# Connective.net
KiCad netlist of a schematic drawn in EasyEDA Pro
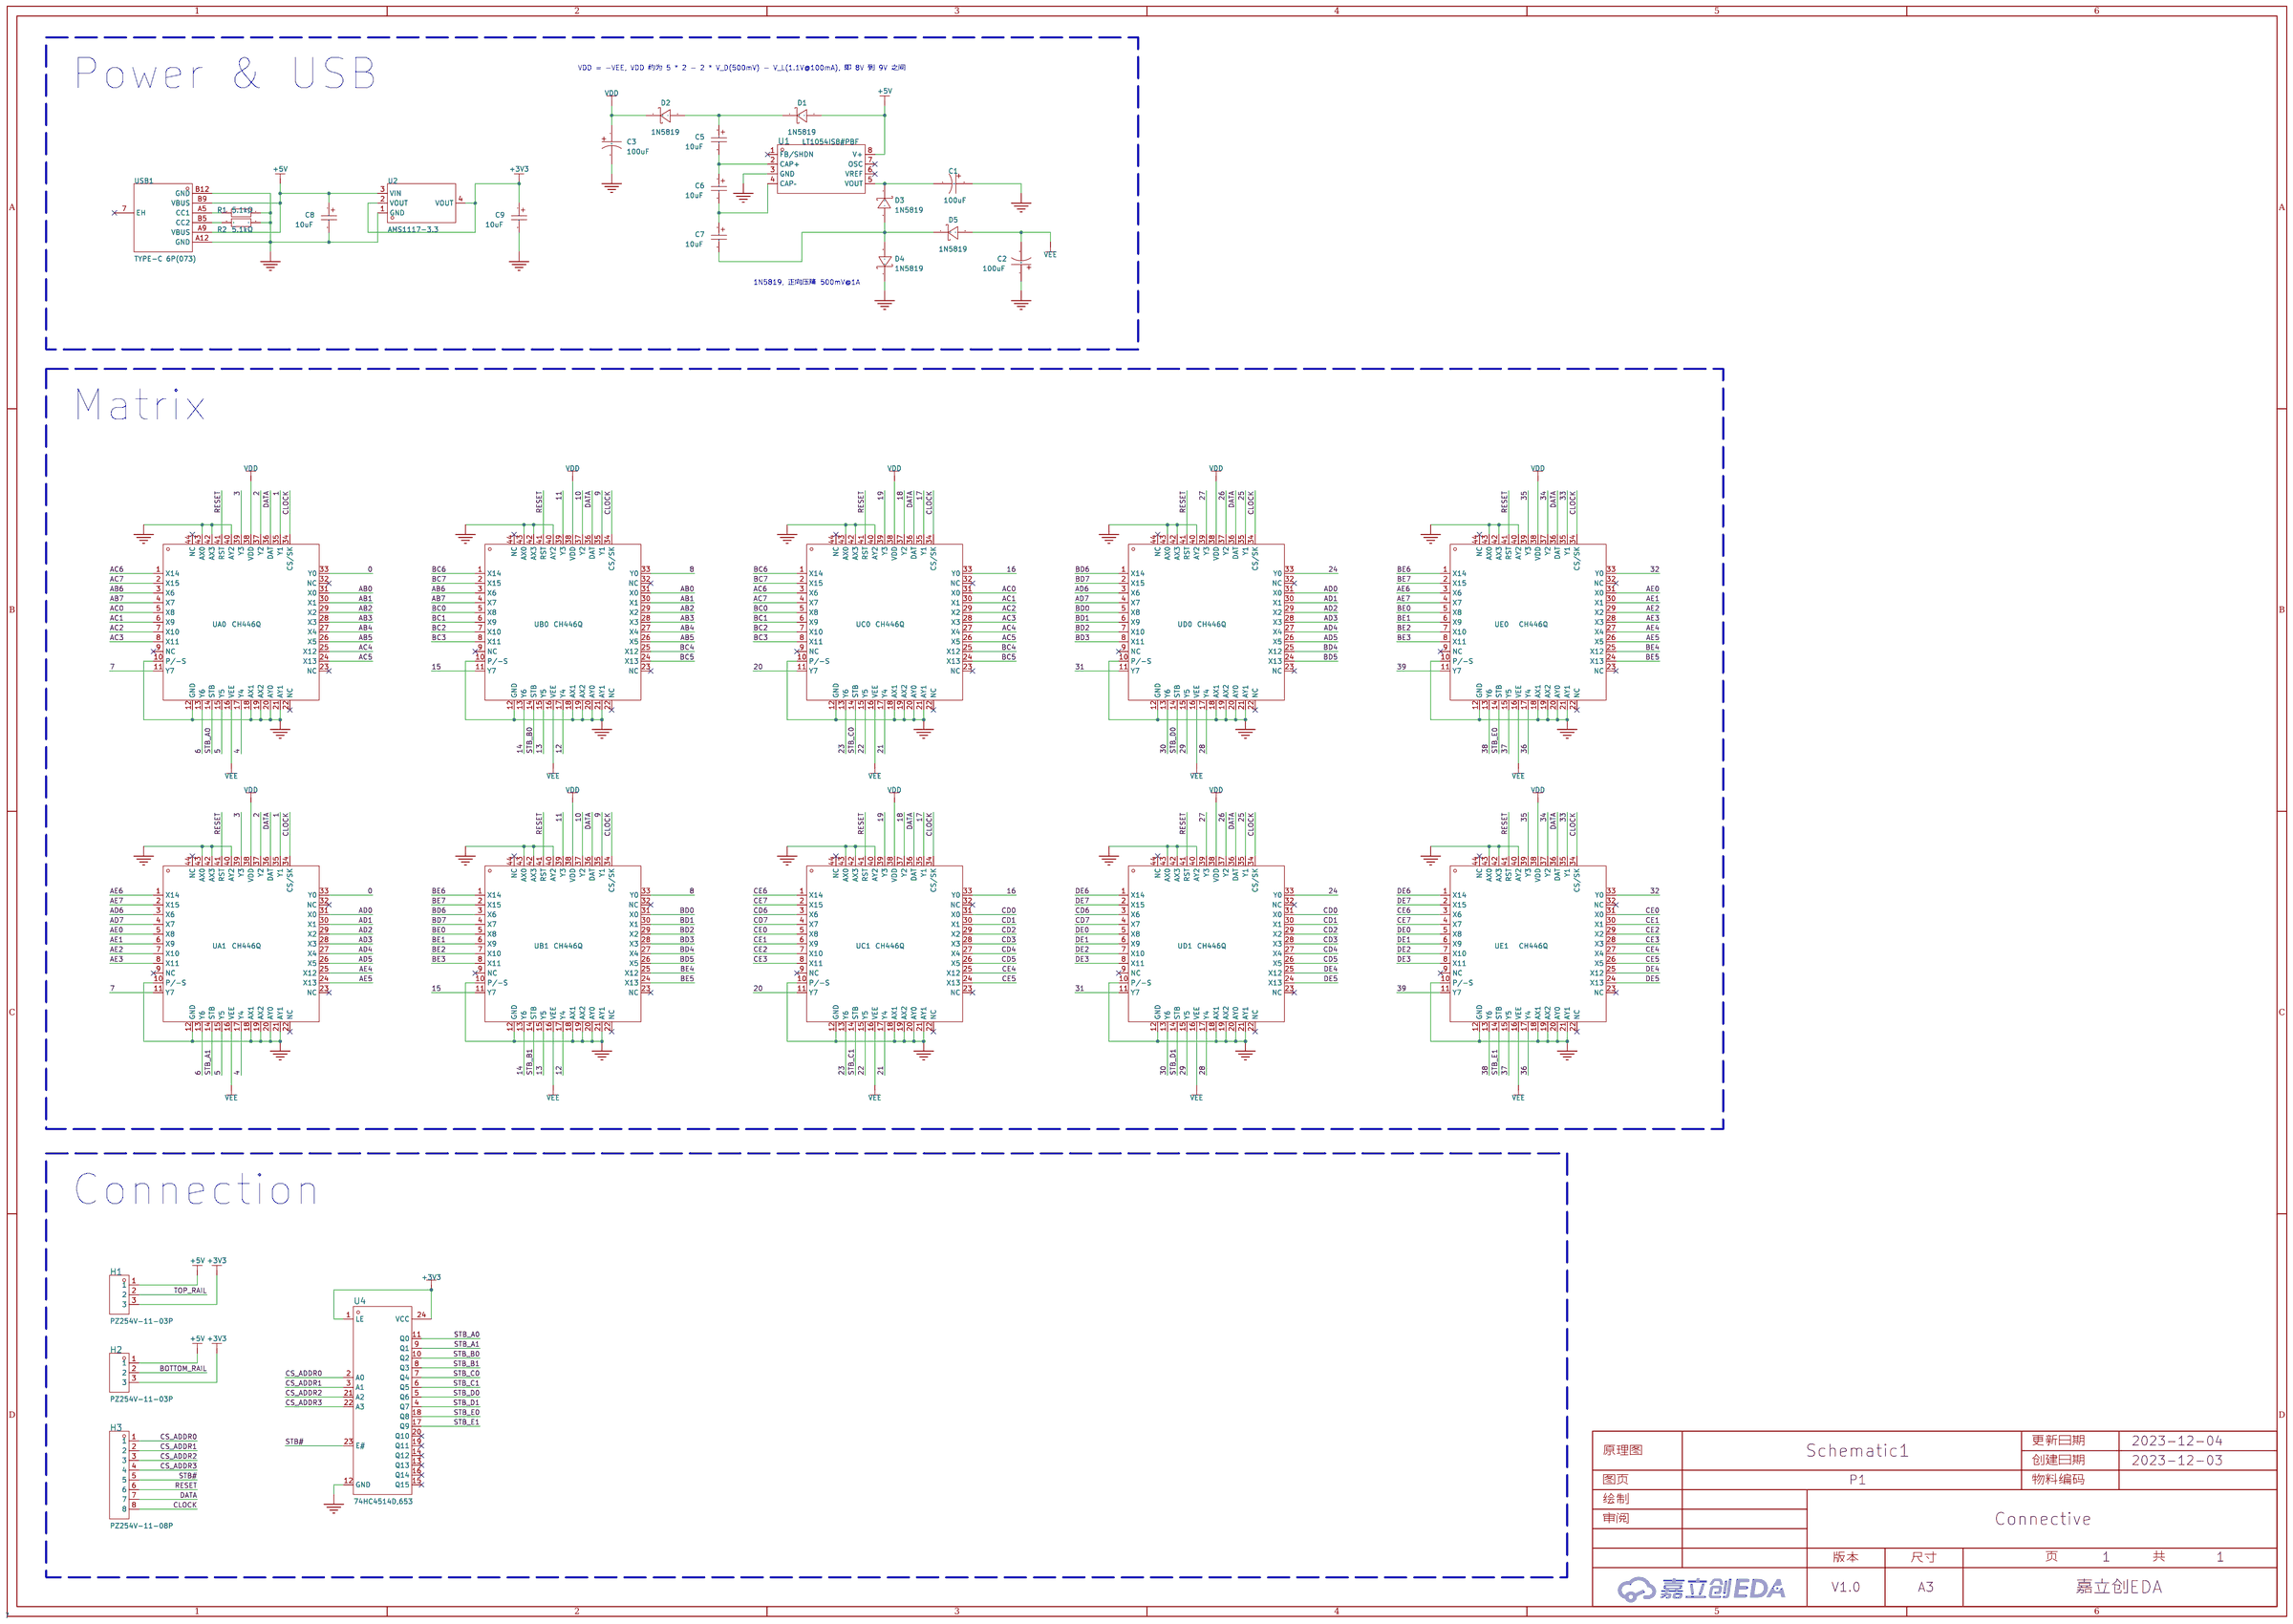
[diagram p0: schematic sheet]

(export (version "E")
  (design (tool "Eeschema 10.0.6"))
  (components
    (comp (ref "C1")
      (value "100uF")
      (footprint "easyedapro:CAP-SMD_L3.5-W2.8")
      (description "容值:100uF;精度:±20%;额定电压:10V;等效串联电阻:3Ω@100kHz;")
      (fields (field (name "Manufacturer Part") "CA45-107M010BT") (field (name "Manufacturer") "TANCAP(容电)"))
      (libsource (lib "easyedapro") (part "CA45-107M010BT"))
    )
    (comp (ref "C2")
      (value "100uF")
      (footprint "easyedapro:CAP-SMD_L3.5-W2.8")
      (description "容值:100uF;精度:±20%;额定电压:10V;等效串联电阻:3Ω@100kHz;")
      (fields (field (name "Manufacturer Part") "CA45-107M010BT") (field (name "Manufacturer") "TANCAP(容电)"))
      (libsource (lib "easyedapro") (part "CA45-107M010BT"))
    )
    (comp (ref "C3")
      (value "100uF")
      (footprint "easyedapro:CAP-SMD_L3.5-W2.8")
      (description "容值:100uF;精度:±20%;额定电压:10V;等效串联电阻:3Ω@100kHz;")
      (fields (field (name "Manufacturer Part") "CA45-107M010BT") (field (name "Manufacturer") "TANCAP(容电)"))
      (libsource (lib "easyedapro") (part "CA45-107M010BT"))
    )
    (comp (ref "C5")
      (value "10uF")
      (footprint "easyedapro:CAP-SMD_L3.2-W1.6-RD")
      (description "容值:10uF;精度:±10%;额定电压:16V;等效串联电阻:10Ω@100kHz;")
      (fields
        (field (name "Manufacturer Part") "CA45-A-16V-10uF-K")
        (field (name "Manufacturer") "CEC(振华新云)")
      )
      (libsource (lib "easyedapro") (part "CA45-A-16V-10UF-K"))
    )
    (comp (ref "C6")
      (value "10uF")
      (footprint "easyedapro:CAP-SMD_L3.2-W1.6-RD")
      (description "容值:10uF;精度:±10%;额定电压:16V;等效串联电阻:10Ω@100kHz;")
      (fields
        (field (name "Manufacturer Part") "CA45-A-16V-10uF-K")
        (field (name "Manufacturer") "CEC(振华新云)")
      )
      (libsource (lib "easyedapro") (part "CA45-A-16V-10UF-K"))
    )
    (comp (ref "C7")
      (value "10uF")
      (footprint "easyedapro:CAP-SMD_L3.2-W1.6-RD")
      (description "容值:10uF;精度:±10%;额定电压:16V;等效串联电阻:10Ω@100kHz;")
      (fields
        (field (name "Manufacturer Part") "CA45-A-16V-10uF-K")
        (field (name "Manufacturer") "CEC(振华新云)")
      )
      (libsource (lib "easyedapro") (part "CA45-A-16V-10UF-K"))
    )
    (comp (ref "C8")
      (value "10uF")
      (footprint "easyedapro:CAP-SMD_L3.2-W1.6-RD")
      (description "容值:10uF;精度:±10%;额定电压:16V;等效串联电阻:10Ω@100kHz;")
      (fields
        (field (name "Manufacturer Part") "CA45-A-16V-10uF-K")
        (field (name "Manufacturer") "CEC(振华新云)")
      )
      (libsource (lib "easyedapro") (part "CA45-A-16V-10UF-K"))
    )
    (comp (ref "C9")
      (value "10uF")
      (footprint "easyedapro:CAP-SMD_L3.2-W1.6-RD")
      (description "容值:10uF;精度:±10%;额定电压:16V;等效串联电阻:10Ω@100kHz;")
      (fields
        (field (name "Manufacturer Part") "CA45-A-16V-10uF-K")
        (field (name "Manufacturer") "CEC(振华新云)")
      )
      (libsource (lib "easyedapro") (part "CA45-A-16V-10UF-K"))
    )
    (comp (ref "D1")
      (value "1N5819")
      (footprint "easyedapro:SMA_L4.4-W2.6-LS5.0-RD")
      (description "直流反向耐压(Vr):40V;平均整流电流(Io):1A;正向压降(Vf):500mV@1A;")
      (fields (field (name "Manufacturer") "KEXIN(科信)"))
      (libsource (lib "easyedapro") (part "1N5819_C437199"))
    )
    (comp (ref "D2")
      (value "1N5819")
      (footprint "easyedapro:SMA_L4.4-W2.6-LS5.0-RD")
      (description "直流反向耐压(Vr):40V;平均整流电流(Io):1A;正向压降(Vf):500mV@1A;")
      (fields (field (name "Manufacturer") "KEXIN(科信)"))
      (libsource (lib "easyedapro") (part "1N5819_C437199"))
    )
    (comp (ref "D3")
      (value "1N5819")
      (footprint "easyedapro:SMA_L4.4-W2.6-LS5.0-RD")
      (description "直流反向耐压(Vr):40V;平均整流电流(Io):1A;正向压降(Vf):500mV@1A;")
      (fields (field (name "Manufacturer") "KEXIN(科信)"))
      (libsource (lib "easyedapro") (part "1N5819_C437199"))
    )
    (comp (ref "D4")
      (value "1N5819")
      (footprint "easyedapro:SMA_L4.4-W2.6-LS5.0-RD")
      (description "直流反向耐压(Vr):40V;平均整流电流(Io):1A;正向压降(Vf):500mV@1A;")
      (fields (field (name "Manufacturer") "KEXIN(科信)"))
      (libsource (lib "easyedapro") (part "1N5819_C437199"))
    )
    (comp (ref "D5")
      (value "1N5819")
      (footprint "easyedapro:SMA_L4.4-W2.6-LS5.0-RD")
      (description "直流反向耐压(Vr):40V;平均整流电流(Io):1A;正向压降(Vf):500mV@1A;")
      (fields (field (name "Manufacturer") "KEXIN(科信)"))
      (libsource (lib "easyedapro") (part "1N5819_C437199"))
    )
    (comp (ref "H1")
      (value "PZ254V-11-03P")
      (footprint "easyedapro:HDR-TH_3P-P2.54-V-M")
      (fields (field (name "Manufacturer") "XFCN(兴飞)"))
      (libsource (lib "easyedapro") (part "PZ254V-11-03P_C2937625"))
    )
    (comp (ref "H2")
      (value "PZ254V-11-03P")
      (footprint "easyedapro:HDR-TH_3P-P2.54-V-M")
      (fields (field (name "Manufacturer") "XFCN(兴飞)"))
      (libsource (lib "easyedapro") (part "PZ254V-11-03P_C2937625"))
    )
    (comp (ref "H3")
      (value "PZ254V-11-08P")
      (footprint "easyedapro:HDR-TH_8P-P2.54-V-M")
      (fields (field (name "Manufacturer") "XFCN(兴飞)"))
      (libsource (lib "easyedapro") (part "PZ254V-11-08P"))
    )
    (comp (ref "R1")
      (value "5.1kΩ")
      (footprint "easyedapro:R0603")
      (description "阻值:5.1kΩ;精度:±1%;功率:100mW;温度系数:±100ppm/°C;电阻类型:厚膜电阻;")
      (fields
        (field (name "Manufacturer Part") "0603WAF5101T5E")
        (field (name "Manufacturer") "UNI-ROYAL(厚声)")
      )
      (libsource (lib "easyedapro") (part "0603WAF5101T5E"))
    )
    (comp (ref "R2")
      (value "5.1kΩ")
      (footprint "easyedapro:R0603")
      (description "阻值:5.1kΩ;精度:±1%;功率:100mW;温度系数:±100ppm/°C;电阻类型:厚膜电阻;")
      (fields
        (field (name "Manufacturer Part") "0603WAF5101T5E")
        (field (name "Manufacturer") "UNI-ROYAL(厚声)")
      )
      (libsource (lib "easyedapro") (part "0603WAF5101T5E"))
    )
    (comp (ref "U1")
      (value "LT1054IS8#PBF")
      (footprint "easyedapro:SO-8_L4.9-W3.9-P1.27-LS6.0-BL")
      (description "功能类型:升压型;输出类型:可调和固定;输入电压:3.5V~15V;输出电压:2.5V~30V;输出电流(最大值):100mA;")
      (fields (field (name "Manufacturer") "ADI(亚德诺)"))
      (libsource (lib "easyedapro") (part "LT1054IS8#PBF"))
    )
    (comp (ref "U2")
      (value "AMS1117-3.3")
      (footprint "easyedapro:SOT-223-3_L6.5-W3.4-P2.30-LS7.0-BR")
      (description "输出类型:固定;最大输入电压:-;输出电压:3.3V;输出电流:1A;电源纹波抑制比(PSRR):72dB@(120Hz);输出极性:正;")
      (fields (field (name "Manufacturer") "AMS"))
      (libsource (lib "easyedapro") (part "AMS1117-3.3"))
    )
    (comp (ref "U4")
      (value "74HC4514D,653")
      (footprint "easyedapro:SOIC-24_L15.4-W7.5-P1.27-LS10.3-BL")
      (description "灌电流(IOL):5.2mA;拉电流(IOH):5.2mA;供电电压:2V~6V;")
      (fields (field (name "Manufacturer") "Nexperia(安世)"))
      (libsource (lib "easyedapro") (part "74HC4514D"))
    )
    (comp (ref "UA0")
      (value "CH446Q")
      (footprint "easyedapro:LQFP-44_L10.0-W10.0-P0.80-LS12.0-BL")
      (description "开关电路:-;")
      (fields (field (name "Manufacturer") "WCH(南京沁恒)"))
      (libsource (lib "easyedapro") (part "CH446Q"))
    )
    (comp (ref "UA1")
      (value "CH446Q")
      (footprint "easyedapro:LQFP-44_L10.0-W10.0-P0.80-LS12.0-BL")
      (description "开关电路:-;")
      (fields (field (name "Manufacturer") "WCH(南京沁恒)"))
      (libsource (lib "easyedapro") (part "CH446Q"))
    )
    (comp (ref "UB0")
      (value "CH446Q")
      (footprint "easyedapro:LQFP-44_L10.0-W10.0-P0.80-LS12.0-BL")
      (description "开关电路:-;")
      (fields (field (name "Manufacturer") "WCH(南京沁恒)"))
      (libsource (lib "easyedapro") (part "CH446Q"))
    )
    (comp (ref "UB1")
      (value "CH446Q")
      (footprint "easyedapro:LQFP-44_L10.0-W10.0-P0.80-LS12.0-BL")
      (description "开关电路:-;")
      (fields (field (name "Manufacturer") "WCH(南京沁恒)"))
      (libsource (lib "easyedapro") (part "CH446Q"))
    )
    (comp (ref "UC0")
      (value "CH446Q")
      (footprint "easyedapro:LQFP-44_L10.0-W10.0-P0.80-LS12.0-BL")
      (description "开关电路:-;")
      (fields (field (name "Manufacturer") "WCH(南京沁恒)"))
      (libsource (lib "easyedapro") (part "CH446Q"))
    )
    (comp (ref "UC1")
      (value "CH446Q")
      (footprint "easyedapro:LQFP-44_L10.0-W10.0-P0.80-LS12.0-BL")
      (description "开关电路:-;")
      (fields (field (name "Manufacturer") "WCH(南京沁恒)"))
      (libsource (lib "easyedapro") (part "CH446Q"))
    )
    (comp (ref "UD0")
      (value "CH446Q")
      (footprint "easyedapro:LQFP-44_L10.0-W10.0-P0.80-LS12.0-BL")
      (description "开关电路:-;")
      (fields (field (name "Manufacturer") "WCH(南京沁恒)"))
      (libsource (lib "easyedapro") (part "CH446Q"))
    )
    (comp (ref "UD1")
      (value "CH446Q")
      (footprint "easyedapro:LQFP-44_L10.0-W10.0-P0.80-LS12.0-BL")
      (description "开关电路:-;")
      (fields (field (name "Manufacturer") "WCH(南京沁恒)"))
      (libsource (lib "easyedapro") (part "CH446Q"))
    )
    (comp (ref "UE0")
      (value "CH446Q")
      (footprint "easyedapro:LQFP-44_L10.0-W10.0-P0.80-LS12.0-BL")
      (description "开关电路:-;")
      (fields (field (name "Manufacturer") "WCH(南京沁恒)"))
      (libsource (lib "easyedapro") (part "CH446Q"))
    )
    (comp (ref "UE1")
      (value "CH446Q")
      (footprint "easyedapro:LQFP-44_L10.0-W10.0-P0.80-LS12.0-BL")
      (description "开关电路:-;")
      (fields (field (name "Manufacturer") "WCH(南京沁恒)"))
      (libsource (lib "easyedapro") (part "CH446Q"))
    )
    (comp (ref "USB1")
      (value "TYPE-C 6P(073)")
      (footprint "easyedapro:TYPE-C-SMD_TYPE-C-6P")
      (description "连接器类型:Type-C;标准:-;公母:母;触点数量:6P;端口数量:1;安装方式:卧贴;额定电流 - 电源:5A;工作温度范围:-25°C~+85°C;")
      (fields (field (name "Manufacturer") "SHOU HAN(首韩)"))
      (libsource (lib "easyedapro") (part "TYPE-C 6P(073)"))
    )
  )
  (nets
    (net (code "1") (name "+3V3") (class "Default")
      (node (ref "C9") (pin "1") (pinfunction "1_1") (pintype "input"))
      (node (ref "H1") (pin "3") (pinfunction "3_3") (pintype "input"))
      (node (ref "H2") (pin "3") (pinfunction "3_3") (pintype "input"))
      (node (ref "U2") (pin "2") (pinfunction "VOUT_2") (pintype "unspecified"))
      (node (ref "U2") (pin "4") (pinfunction "VOUT_4") (pintype "unspecified"))
      (node (ref "U4") (pin "1") (pinfunction "LE_1") (pintype "input"))
      (node (ref "U4") (pin "24") (pinfunction "VCC_24") (pintype "input"))
    )
    (net (code "2") (name "+5V") (class "Default")
      (node (ref "C8") (pin "1") (pinfunction "1_1") (pintype "input"))
      (node (ref "D1") (pin "2") (pinfunction "A_2") (pintype "unspecified"))
      (node (ref "H1") (pin "1") (pinfunction "1_1") (pintype "input"))
      (node (ref "H2") (pin "1") (pinfunction "1_1") (pintype "input"))
      (node (ref "U1") (pin "8") (pinfunction "V+_8") (pintype "input"))
      (node (ref "U2") (pin "3") (pinfunction "VIN_3") (pintype "unspecified"))
      (node (ref "USB1") (pin "A9") (pinfunction "VBUS_A9") (pintype "unspecified"))
      (node (ref "USB1") (pin "B9") (pinfunction "VBUS_B9") (pintype "unspecified"))
    )
    (net (code "3") (name "/0") (class "Default")
      (node (ref "UA0") (pin "33") (pinfunction "Y0_33") (pintype "unspecified"))
      (node (ref "UA1") (pin "33") (pinfunction "Y0_33") (pintype "unspecified"))
    )
    (net (code "4") (name "/1") (class "Default")
      (node (ref "UA0") (pin "35") (pinfunction "Y1_35") (pintype "unspecified"))
      (node (ref "UA1") (pin "35") (pinfunction "Y1_35") (pintype "unspecified"))
    )
    (net (code "5") (name "/2") (class "Default")
      (node (ref "UA0") (pin "37") (pinfunction "Y2_37") (pintype "unspecified"))
      (node (ref "UA1") (pin "37") (pinfunction "Y2_37") (pintype "unspecified"))
    )
    (net (code "6") (name "/3") (class "Default")
      (node (ref "UA0") (pin "39") (pinfunction "Y3_39") (pintype "unspecified"))
      (node (ref "UA1") (pin "39") (pinfunction "Y3_39") (pintype "unspecified"))
    )
    (net (code "7") (name "/4") (class "Default")
      (node (ref "UA0") (pin "17") (pinfunction "Y4_17") (pintype "unspecified"))
      (node (ref "UA1") (pin "17") (pinfunction "Y4_17") (pintype "unspecified"))
    )
    (net (code "8") (name "/5") (class "Default")
      (node (ref "UA0") (pin "15") (pinfunction "Y5_15") (pintype "unspecified"))
      (node (ref "UA1") (pin "15") (pinfunction "Y5_15") (pintype "unspecified"))
    )
    (net (code "9") (name "/6") (class "Default")
      (node (ref "UA0") (pin "13") (pinfunction "Y6_13") (pintype "unspecified"))
      (node (ref "UA1") (pin "13") (pinfunction "Y6_13") (pintype "unspecified"))
    )
    (net (code "10") (name "/7") (class "Default")
      (node (ref "UA0") (pin "11") (pinfunction "Y7_11") (pintype "unspecified"))
      (node (ref "UA1") (pin "11") (pinfunction "Y7_11") (pintype "unspecified"))
    )
    (net (code "11") (name "/8") (class "Default")
      (node (ref "UB0") (pin "33") (pinfunction "Y0_33") (pintype "unspecified"))
      (node (ref "UB1") (pin "33") (pinfunction "Y0_33") (pintype "unspecified"))
    )
    (net (code "12") (name "/9") (class "Default")
      (node (ref "UB0") (pin "35") (pinfunction "Y1_35") (pintype "unspecified"))
      (node (ref "UB1") (pin "35") (pinfunction "Y1_35") (pintype "unspecified"))
    )
    (net (code "13") (name "/10") (class "Default")
      (node (ref "UB0") (pin "37") (pinfunction "Y2_37") (pintype "unspecified"))
      (node (ref "UB1") (pin "37") (pinfunction "Y2_37") (pintype "unspecified"))
    )
    (net (code "14") (name "/11") (class "Default")
      (node (ref "UB0") (pin "39") (pinfunction "Y3_39") (pintype "unspecified"))
      (node (ref "UB1") (pin "39") (pinfunction "Y3_39") (pintype "unspecified"))
    )
    (net (code "15") (name "/12") (class "Default")
      (node (ref "UB0") (pin "17") (pinfunction "Y4_17") (pintype "unspecified"))
      (node (ref "UB1") (pin "17") (pinfunction "Y4_17") (pintype "unspecified"))
    )
    (net (code "16") (name "/13") (class "Default")
      (node (ref "UB0") (pin "15") (pinfunction "Y5_15") (pintype "unspecified"))
      (node (ref "UB1") (pin "15") (pinfunction "Y5_15") (pintype "unspecified"))
    )
    (net (code "17") (name "/14") (class "Default")
      (node (ref "UB0") (pin "13") (pinfunction "Y6_13") (pintype "unspecified"))
      (node (ref "UB1") (pin "13") (pinfunction "Y6_13") (pintype "unspecified"))
    )
    (net (code "18") (name "/15") (class "Default")
      (node (ref "UB0") (pin "11") (pinfunction "Y7_11") (pintype "unspecified"))
      (node (ref "UB1") (pin "11") (pinfunction "Y7_11") (pintype "unspecified"))
    )
    (net (code "19") (name "/16") (class "Default")
      (node (ref "UC0") (pin "33") (pinfunction "Y0_33") (pintype "unspecified"))
      (node (ref "UC1") (pin "33") (pinfunction "Y0_33") (pintype "unspecified"))
    )
    (net (code "20") (name "/17") (class "Default")
      (node (ref "UC0") (pin "35") (pinfunction "Y1_35") (pintype "unspecified"))
      (node (ref "UC1") (pin "35") (pinfunction "Y1_35") (pintype "unspecified"))
    )
    (net (code "21") (name "/18") (class "Default")
      (node (ref "UC0") (pin "37") (pinfunction "Y2_37") (pintype "unspecified"))
      (node (ref "UC1") (pin "37") (pinfunction "Y2_37") (pintype "unspecified"))
    )
    (net (code "22") (name "/19") (class "Default")
      (node (ref "UC0") (pin "39") (pinfunction "Y3_39") (pintype "unspecified"))
      (node (ref "UC1") (pin "39") (pinfunction "Y3_39") (pintype "unspecified"))
    )
    (net (code "23") (name "/20") (class "Default")
      (node (ref "UC0") (pin "11") (pinfunction "Y7_11") (pintype "unspecified"))
      (node (ref "UC1") (pin "11") (pinfunction "Y7_11") (pintype "unspecified"))
    )
    (net (code "24") (name "/21") (class "Default")
      (node (ref "UC0") (pin "17") (pinfunction "Y4_17") (pintype "unspecified"))
      (node (ref "UC1") (pin "17") (pinfunction "Y4_17") (pintype "unspecified"))
    )
    (net (code "25") (name "/22") (class "Default")
      (node (ref "UC0") (pin "15") (pinfunction "Y5_15") (pintype "unspecified"))
      (node (ref "UC1") (pin "15") (pinfunction "Y5_15") (pintype "unspecified"))
    )
    (net (code "26") (name "/23") (class "Default")
      (node (ref "UC0") (pin "13") (pinfunction "Y6_13") (pintype "unspecified"))
      (node (ref "UC1") (pin "13") (pinfunction "Y6_13") (pintype "unspecified"))
    )
    (net (code "27") (name "/24") (class "Default")
      (node (ref "UD0") (pin "33") (pinfunction "Y0_33") (pintype "unspecified"))
      (node (ref "UD1") (pin "33") (pinfunction "Y0_33") (pintype "unspecified"))
    )
    (net (code "28") (name "/25") (class "Default")
      (node (ref "UD0") (pin "35") (pinfunction "Y1_35") (pintype "unspecified"))
      (node (ref "UD1") (pin "35") (pinfunction "Y1_35") (pintype "unspecified"))
    )
    (net (code "29") (name "/26") (class "Default")
      (node (ref "UD0") (pin "37") (pinfunction "Y2_37") (pintype "unspecified"))
      (node (ref "UD1") (pin "37") (pinfunction "Y2_37") (pintype "unspecified"))
    )
    (net (code "30") (name "/27") (class "Default")
      (node (ref "UD0") (pin "39") (pinfunction "Y3_39") (pintype "unspecified"))
      (node (ref "UD1") (pin "39") (pinfunction "Y3_39") (pintype "unspecified"))
    )
    (net (code "31") (name "/28") (class "Default")
      (node (ref "UD0") (pin "17") (pinfunction "Y4_17") (pintype "unspecified"))
      (node (ref "UD1") (pin "17") (pinfunction "Y4_17") (pintype "unspecified"))
    )
    (net (code "32") (name "/29") (class "Default")
      (node (ref "UD0") (pin "15") (pinfunction "Y5_15") (pintype "unspecified"))
      (node (ref "UD1") (pin "15") (pinfunction "Y5_15") (pintype "unspecified"))
    )
    (net (code "33") (name "/30") (class "Default")
      (node (ref "UD0") (pin "13") (pinfunction "Y6_13") (pintype "unspecified"))
      (node (ref "UD1") (pin "13") (pinfunction "Y6_13") (pintype "unspecified"))
    )
    (net (code "34") (name "/31") (class "Default")
      (node (ref "UD0") (pin "11") (pinfunction "Y7_11") (pintype "unspecified"))
      (node (ref "UD1") (pin "11") (pinfunction "Y7_11") (pintype "unspecified"))
    )
    (net (code "35") (name "/32") (class "Default")
      (node (ref "UE0") (pin "33") (pinfunction "Y0_33") (pintype "unspecified"))
      (node (ref "UE1") (pin "33") (pinfunction "Y0_33") (pintype "unspecified"))
    )
    (net (code "36") (name "/33") (class "Default")
      (node (ref "UE0") (pin "35") (pinfunction "Y1_35") (pintype "unspecified"))
      (node (ref "UE1") (pin "35") (pinfunction "Y1_35") (pintype "unspecified"))
    )
    (net (code "37") (name "/34") (class "Default")
      (node (ref "UE0") (pin "37") (pinfunction "Y2_37") (pintype "unspecified"))
      (node (ref "UE1") (pin "37") (pinfunction "Y2_37") (pintype "unspecified"))
    )
    (net (code "38") (name "/35") (class "Default")
      (node (ref "UE0") (pin "39") (pinfunction "Y3_39") (pintype "unspecified"))
      (node (ref "UE1") (pin "39") (pinfunction "Y3_39") (pintype "unspecified"))
    )
    (net (code "39") (name "/36") (class "Default")
      (node (ref "UE0") (pin "17") (pinfunction "Y4_17") (pintype "unspecified"))
      (node (ref "UE1") (pin "17") (pinfunction "Y4_17") (pintype "unspecified"))
    )
    (net (code "40") (name "/37") (class "Default")
      (node (ref "UE0") (pin "15") (pinfunction "Y5_15") (pintype "unspecified"))
      (node (ref "UE1") (pin "15") (pinfunction "Y5_15") (pintype "unspecified"))
    )
    (net (code "41") (name "/38") (class "Default")
      (node (ref "UE0") (pin "13") (pinfunction "Y6_13") (pintype "unspecified"))
      (node (ref "UE1") (pin "13") (pinfunction "Y6_13") (pintype "unspecified"))
    )
    (net (code "42") (name "/39") (class "Default")
      (node (ref "UE0") (pin "11") (pinfunction "Y7_11") (pintype "unspecified"))
      (node (ref "UE1") (pin "11") (pinfunction "Y7_11") (pintype "unspecified"))
    )
    (net (code "43") (name "/AB0") (class "Default")
      (node (ref "UA0") (pin "31") (pinfunction "X0_31") (pintype "unspecified"))
      (node (ref "UB0") (pin "31") (pinfunction "X0_31") (pintype "unspecified"))
    )
    (net (code "44") (name "/AB1") (class "Default")
      (node (ref "UA0") (pin "30") (pinfunction "X1_30") (pintype "unspecified"))
      (node (ref "UB0") (pin "30") (pinfunction "X1_30") (pintype "unspecified"))
    )
    (net (code "45") (name "/AB2") (class "Default")
      (node (ref "UA0") (pin "29") (pinfunction "X2_29") (pintype "unspecified"))
      (node (ref "UB0") (pin "29") (pinfunction "X2_29") (pintype "unspecified"))
    )
    (net (code "46") (name "/AB3") (class "Default")
      (node (ref "UA0") (pin "28") (pinfunction "X3_28") (pintype "unspecified"))
      (node (ref "UB0") (pin "28") (pinfunction "X3_28") (pintype "unspecified"))
    )
    (net (code "47") (name "/AB4") (class "Default")
      (node (ref "UA0") (pin "27") (pinfunction "X4_27") (pintype "unspecified"))
      (node (ref "UB0") (pin "27") (pinfunction "X4_27") (pintype "unspecified"))
    )
    (net (code "48") (name "/AB5") (class "Default")
      (node (ref "UA0") (pin "26") (pinfunction "X5_26") (pintype "unspecified"))
      (node (ref "UB0") (pin "26") (pinfunction "X5_26") (pintype "unspecified"))
    )
    (net (code "49") (name "/AB6") (class "Default")
      (node (ref "UA0") (pin "3") (pinfunction "X6_3") (pintype "unspecified"))
      (node (ref "UB0") (pin "3") (pinfunction "X6_3") (pintype "unspecified"))
    )
    (net (code "50") (name "/AB7") (class "Default")
      (node (ref "UA0") (pin "4") (pinfunction "X7_4") (pintype "unspecified"))
      (node (ref "UB0") (pin "4") (pinfunction "X7_4") (pintype "unspecified"))
    )
    (net (code "51") (name "/AC0") (class "Default")
      (node (ref "UA0") (pin "5") (pinfunction "X8_5") (pintype "unspecified"))
      (node (ref "UC0") (pin "31") (pinfunction "X0_31") (pintype "unspecified"))
    )
    (net (code "52") (name "/AC1") (class "Default")
      (node (ref "UA0") (pin "6") (pinfunction "X9_6") (pintype "unspecified"))
      (node (ref "UC0") (pin "30") (pinfunction "X1_30") (pintype "unspecified"))
    )
    (net (code "53") (name "/AC2") (class "Default")
      (node (ref "UA0") (pin "7") (pinfunction "X10_7") (pintype "unspecified"))
      (node (ref "UC0") (pin "29") (pinfunction "X2_29") (pintype "unspecified"))
    )
    (net (code "54") (name "/AC3") (class "Default")
      (node (ref "UA0") (pin "8") (pinfunction "X11_8") (pintype "unspecified"))
      (node (ref "UC0") (pin "28") (pinfunction "X3_28") (pintype "unspecified"))
    )
    (net (code "55") (name "/AC4") (class "Default")
      (node (ref "UA0") (pin "25") (pinfunction "X12_25") (pintype "unspecified"))
      (node (ref "UC0") (pin "27") (pinfunction "X4_27") (pintype "unspecified"))
    )
    (net (code "56") (name "/AC5") (class "Default")
      (node (ref "UA0") (pin "24") (pinfunction "X13_24") (pintype "unspecified"))
      (node (ref "UC0") (pin "26") (pinfunction "X5_26") (pintype "unspecified"))
    )
    (net (code "57") (name "/AC6") (class "Default")
      (node (ref "UA0") (pin "1") (pinfunction "X14_1") (pintype "unspecified"))
      (node (ref "UC0") (pin "3") (pinfunction "X6_3") (pintype "unspecified"))
    )
    (net (code "58") (name "/AC7") (class "Default")
      (node (ref "UA0") (pin "2") (pinfunction "X15_2") (pintype "unspecified"))
      (node (ref "UC0") (pin "4") (pinfunction "X7_4") (pintype "unspecified"))
    )
    (net (code "59") (name "/AD0") (class "Default")
      (node (ref "UA1") (pin "31") (pinfunction "X0_31") (pintype "unspecified"))
      (node (ref "UD0") (pin "31") (pinfunction "X0_31") (pintype "unspecified"))
    )
    (net (code "60") (name "/AD1") (class "Default")
      (node (ref "UA1") (pin "30") (pinfunction "X1_30") (pintype "unspecified"))
      (node (ref "UD0") (pin "30") (pinfunction "X1_30") (pintype "unspecified"))
    )
    (net (code "61") (name "/AD2") (class "Default")
      (node (ref "UA1") (pin "29") (pinfunction "X2_29") (pintype "unspecified"))
      (node (ref "UD0") (pin "29") (pinfunction "X2_29") (pintype "unspecified"))
    )
    (net (code "62") (name "/AD3") (class "Default")
      (node (ref "UA1") (pin "28") (pinfunction "X3_28") (pintype "unspecified"))
      (node (ref "UD0") (pin "28") (pinfunction "X3_28") (pintype "unspecified"))
    )
    (net (code "63") (name "/AD4") (class "Default")
      (node (ref "UA1") (pin "27") (pinfunction "X4_27") (pintype "unspecified"))
      (node (ref "UD0") (pin "27") (pinfunction "X4_27") (pintype "unspecified"))
    )
    (net (code "64") (name "/AD5") (class "Default")
      (node (ref "UA1") (pin "26") (pinfunction "X5_26") (pintype "unspecified"))
      (node (ref "UD0") (pin "26") (pinfunction "X5_26") (pintype "unspecified"))
    )
    (net (code "65") (name "/AD6") (class "Default")
      (node (ref "UA1") (pin "3") (pinfunction "X6_3") (pintype "unspecified"))
      (node (ref "UD0") (pin "3") (pinfunction "X6_3") (pintype "unspecified"))
    )
    (net (code "66") (name "/AD7") (class "Default")
      (node (ref "UA1") (pin "4") (pinfunction "X7_4") (pintype "unspecified"))
      (node (ref "UD0") (pin "4") (pinfunction "X7_4") (pintype "unspecified"))
    )
    (net (code "67") (name "/AE0") (class "Default")
      (node (ref "UA1") (pin "5") (pinfunction "X8_5") (pintype "unspecified"))
      (node (ref "UE0") (pin "31") (pinfunction "X0_31") (pintype "unspecified"))
    )
    (net (code "68") (name "/AE1") (class "Default")
      (node (ref "UA1") (pin "6") (pinfunction "X9_6") (pintype "unspecified"))
      (node (ref "UE0") (pin "30") (pinfunction "X1_30") (pintype "unspecified"))
    )
    (net (code "69") (name "/AE2") (class "Default")
      (node (ref "UA1") (pin "7") (pinfunction "X10_7") (pintype "unspecified"))
      (node (ref "UE0") (pin "29") (pinfunction "X2_29") (pintype "unspecified"))
    )
    (net (code "70") (name "/AE3") (class "Default")
      (node (ref "UA1") (pin "8") (pinfunction "X11_8") (pintype "unspecified"))
      (node (ref "UE0") (pin "28") (pinfunction "X3_28") (pintype "unspecified"))
    )
    (net (code "71") (name "/AE4") (class "Default")
      (node (ref "UA1") (pin "25") (pinfunction "X12_25") (pintype "unspecified"))
      (node (ref "UE0") (pin "27") (pinfunction "X4_27") (pintype "unspecified"))
    )
    (net (code "72") (name "/AE5") (class "Default")
      (node (ref "UA1") (pin "24") (pinfunction "X13_24") (pintype "unspecified"))
      (node (ref "UE0") (pin "26") (pinfunction "X5_26") (pintype "unspecified"))
    )
    (net (code "73") (name "/AE6") (class "Default")
      (node (ref "UA1") (pin "1") (pinfunction "X14_1") (pintype "unspecified"))
      (node (ref "UE0") (pin "3") (pinfunction "X6_3") (pintype "unspecified"))
    )
    (net (code "74") (name "/AE7") (class "Default")
      (node (ref "UA1") (pin "2") (pinfunction "X15_2") (pintype "unspecified"))
      (node (ref "UE0") (pin "4") (pinfunction "X7_4") (pintype "unspecified"))
    )
    (net (code "75") (name "/BC0") (class "Default")
      (node (ref "UB0") (pin "5") (pinfunction "X8_5") (pintype "unspecified"))
      (node (ref "UC0") (pin "5") (pinfunction "X8_5") (pintype "unspecified"))
    )
    (net (code "76") (name "/BC1") (class "Default")
      (node (ref "UB0") (pin "6") (pinfunction "X9_6") (pintype "unspecified"))
      (node (ref "UC0") (pin "6") (pinfunction "X9_6") (pintype "unspecified"))
    )
    (net (code "77") (name "/BC2") (class "Default")
      (node (ref "UB0") (pin "7") (pinfunction "X10_7") (pintype "unspecified"))
      (node (ref "UC0") (pin "7") (pinfunction "X10_7") (pintype "unspecified"))
    )
    (net (code "78") (name "/BC3") (class "Default")
      (node (ref "UB0") (pin "8") (pinfunction "X11_8") (pintype "unspecified"))
      (node (ref "UC0") (pin "8") (pinfunction "X11_8") (pintype "unspecified"))
    )
    (net (code "79") (name "/BC4") (class "Default")
      (node (ref "UB0") (pin "25") (pinfunction "X12_25") (pintype "unspecified"))
      (node (ref "UC0") (pin "25") (pinfunction "X12_25") (pintype "unspecified"))
    )
    (net (code "80") (name "/BC5") (class "Default")
      (node (ref "UB0") (pin "24") (pinfunction "X13_24") (pintype "unspecified"))
      (node (ref "UC0") (pin "24") (pinfunction "X13_24") (pintype "unspecified"))
    )
    (net (code "81") (name "/BC6") (class "Default")
      (node (ref "UB0") (pin "1") (pinfunction "X14_1") (pintype "unspecified"))
      (node (ref "UC0") (pin "1") (pinfunction "X14_1") (pintype "unspecified"))
    )
    (net (code "82") (name "/BC7") (class "Default")
      (node (ref "UB0") (pin "2") (pinfunction "X15_2") (pintype "unspecified"))
      (node (ref "UC0") (pin "2") (pinfunction "X15_2") (pintype "unspecified"))
    )
    (net (code "83") (name "/BD0") (class "Default")
      (node (ref "UB1") (pin "31") (pinfunction "X0_31") (pintype "unspecified"))
      (node (ref "UD0") (pin "5") (pinfunction "X8_5") (pintype "unspecified"))
    )
    (net (code "84") (name "/BD1") (class "Default")
      (node (ref "UB1") (pin "30") (pinfunction "X1_30") (pintype "unspecified"))
      (node (ref "UD0") (pin "6") (pinfunction "X9_6") (pintype "unspecified"))
    )
    (net (code "85") (name "/BD2") (class "Default")
      (node (ref "UB1") (pin "29") (pinfunction "X2_29") (pintype "unspecified"))
      (node (ref "UD0") (pin "7") (pinfunction "X10_7") (pintype "unspecified"))
    )
    (net (code "86") (name "/BD3") (class "Default")
      (node (ref "UB1") (pin "28") (pinfunction "X3_28") (pintype "unspecified"))
      (node (ref "UD0") (pin "8") (pinfunction "X11_8") (pintype "unspecified"))
    )
    (net (code "87") (name "/BD4") (class "Default")
      (node (ref "UB1") (pin "27") (pinfunction "X4_27") (pintype "unspecified"))
      (node (ref "UD0") (pin "25") (pinfunction "X12_25") (pintype "unspecified"))
    )
    (net (code "88") (name "/BD5") (class "Default")
      (node (ref "UB1") (pin "26") (pinfunction "X5_26") (pintype "unspecified"))
      (node (ref "UD0") (pin "24") (pinfunction "X13_24") (pintype "unspecified"))
    )
    (net (code "89") (name "/BD6") (class "Default")
      (node (ref "UB1") (pin "3") (pinfunction "X6_3") (pintype "unspecified"))
      (node (ref "UD0") (pin "1") (pinfunction "X14_1") (pintype "unspecified"))
    )
    (net (code "90") (name "/BD7") (class "Default")
      (node (ref "UB1") (pin "4") (pinfunction "X7_4") (pintype "unspecified"))
      (node (ref "UD0") (pin "2") (pinfunction "X15_2") (pintype "unspecified"))
    )
    (net (code "91") (name "/BE0") (class "Default")
      (node (ref "UB1") (pin "5") (pinfunction "X8_5") (pintype "unspecified"))
      (node (ref "UE0") (pin "5") (pinfunction "X8_5") (pintype "unspecified"))
    )
    (net (code "92") (name "/BE1") (class "Default")
      (node (ref "UB1") (pin "6") (pinfunction "X9_6") (pintype "unspecified"))
      (node (ref "UE0") (pin "6") (pinfunction "X9_6") (pintype "unspecified"))
    )
    (net (code "93") (name "/BE2") (class "Default")
      (node (ref "UB1") (pin "7") (pinfunction "X10_7") (pintype "unspecified"))
      (node (ref "UE0") (pin "7") (pinfunction "X10_7") (pintype "unspecified"))
    )
    (net (code "94") (name "/BE3") (class "Default")
      (node (ref "UB1") (pin "8") (pinfunction "X11_8") (pintype "unspecified"))
      (node (ref "UE0") (pin "8") (pinfunction "X11_8") (pintype "unspecified"))
    )
    (net (code "95") (name "/BE4") (class "Default")
      (node (ref "UB1") (pin "25") (pinfunction "X12_25") (pintype "unspecified"))
      (node (ref "UE0") (pin "25") (pinfunction "X12_25") (pintype "unspecified"))
    )
    (net (code "96") (name "/BE5") (class "Default")
      (node (ref "UB1") (pin "24") (pinfunction "X13_24") (pintype "unspecified"))
      (node (ref "UE0") (pin "24") (pinfunction "X13_24") (pintype "unspecified"))
    )
    (net (code "97") (name "/BE6") (class "Default")
      (node (ref "UB1") (pin "1") (pinfunction "X14_1") (pintype "unspecified"))
      (node (ref "UE0") (pin "1") (pinfunction "X14_1") (pintype "unspecified"))
    )
    (net (code "98") (name "/BE7") (class "Default")
      (node (ref "UB1") (pin "2") (pinfunction "X15_2") (pintype "unspecified"))
      (node (ref "UE0") (pin "2") (pinfunction "X15_2") (pintype "unspecified"))
    )
    (net (code "99") (name "/BOTTOM_RAIL") (class "Default")
      (node (ref "H2") (pin "2") (pinfunction "2_2") (pintype "input"))
    )
    (net (code "100") (name "/CD0") (class "Default")
      (node (ref "UC1") (pin "31") (pinfunction "X0_31") (pintype "unspecified"))
      (node (ref "UD1") (pin "31") (pinfunction "X0_31") (pintype "unspecified"))
    )
    (net (code "101") (name "/CD1") (class "Default")
      (node (ref "UC1") (pin "30") (pinfunction "X1_30") (pintype "unspecified"))
      (node (ref "UD1") (pin "30") (pinfunction "X1_30") (pintype "unspecified"))
    )
    (net (code "102") (name "/CD2") (class "Default")
      (node (ref "UC1") (pin "29") (pinfunction "X2_29") (pintype "unspecified"))
      (node (ref "UD1") (pin "29") (pinfunction "X2_29") (pintype "unspecified"))
    )
    (net (code "103") (name "/CD3") (class "Default")
      (node (ref "UC1") (pin "28") (pinfunction "X3_28") (pintype "unspecified"))
      (node (ref "UD1") (pin "28") (pinfunction "X3_28") (pintype "unspecified"))
    )
    (net (code "104") (name "/CD4") (class "Default")
      (node (ref "UC1") (pin "27") (pinfunction "X4_27") (pintype "unspecified"))
      (node (ref "UD1") (pin "27") (pinfunction "X4_27") (pintype "unspecified"))
    )
    (net (code "105") (name "/CD5") (class "Default")
      (node (ref "UC1") (pin "26") (pinfunction "X5_26") (pintype "unspecified"))
      (node (ref "UD1") (pin "26") (pinfunction "X5_26") (pintype "unspecified"))
    )
    (net (code "106") (name "/CD6") (class "Default")
      (node (ref "UC1") (pin "3") (pinfunction "X6_3") (pintype "unspecified"))
      (node (ref "UD1") (pin "3") (pinfunction "X6_3") (pintype "unspecified"))
    )
    (net (code "107") (name "/CD7") (class "Default")
      (node (ref "UC1") (pin "4") (pinfunction "X7_4") (pintype "unspecified"))
      (node (ref "UD1") (pin "4") (pinfunction "X7_4") (pintype "unspecified"))
    )
    (net (code "108") (name "/CE0") (class "Default")
      (node (ref "UC1") (pin "5") (pinfunction "X8_5") (pintype "unspecified"))
      (node (ref "UE1") (pin "31") (pinfunction "X0_31") (pintype "unspecified"))
    )
    (net (code "109") (name "/CE1") (class "Default")
      (node (ref "UC1") (pin "6") (pinfunction "X9_6") (pintype "unspecified"))
      (node (ref "UE1") (pin "30") (pinfunction "X1_30") (pintype "unspecified"))
    )
    (net (code "110") (name "/CE2") (class "Default")
      (node (ref "UC1") (pin "7") (pinfunction "X10_7") (pintype "unspecified"))
      (node (ref "UE1") (pin "29") (pinfunction "X2_29") (pintype "unspecified"))
    )
    (net (code "111") (name "/CE3") (class "Default")
      (node (ref "UC1") (pin "8") (pinfunction "X11_8") (pintype "unspecified"))
      (node (ref "UE1") (pin "28") (pinfunction "X3_28") (pintype "unspecified"))
    )
    (net (code "112") (name "/CE4") (class "Default")
      (node (ref "UC1") (pin "25") (pinfunction "X12_25") (pintype "unspecified"))
      (node (ref "UE1") (pin "27") (pinfunction "X4_27") (pintype "unspecified"))
    )
    (net (code "113") (name "/CE5") (class "Default")
      (node (ref "UC1") (pin "24") (pinfunction "X13_24") (pintype "unspecified"))
      (node (ref "UE1") (pin "26") (pinfunction "X5_26") (pintype "unspecified"))
    )
    (net (code "114") (name "/CE6") (class "Default")
      (node (ref "UC1") (pin "1") (pinfunction "X14_1") (pintype "unspecified"))
      (node (ref "UE1") (pin "3") (pinfunction "X6_3") (pintype "unspecified"))
    )
    (net (code "115") (name "/CE7") (class "Default")
      (node (ref "UC1") (pin "2") (pinfunction "X15_2") (pintype "unspecified"))
      (node (ref "UE1") (pin "4") (pinfunction "X7_4") (pintype "unspecified"))
    )
    (net (code "116") (name "/CLOCK") (class "Default")
      (node (ref "H3") (pin "8") (pinfunction "8_8") (pintype "input"))
      (node (ref "UA0") (pin "34") (pinfunction "CS/SK_34") (pintype "unspecified"))
      (node (ref "UA1") (pin "34") (pinfunction "CS/SK_34") (pintype "unspecified"))
      (node (ref "UB0") (pin "34") (pinfunction "CS/SK_34") (pintype "unspecified"))
      (node (ref "UB1") (pin "34") (pinfunction "CS/SK_34") (pintype "unspecified"))
      (node (ref "UC0") (pin "34") (pinfunction "CS/SK_34") (pintype "unspecified"))
      (node (ref "UC1") (pin "34") (pinfunction "CS/SK_34") (pintype "unspecified"))
      (node (ref "UD0") (pin "34") (pinfunction "CS/SK_34") (pintype "unspecified"))
      (node (ref "UD1") (pin "34") (pinfunction "CS/SK_34") (pintype "unspecified"))
      (node (ref "UE0") (pin "34") (pinfunction "CS/SK_34") (pintype "unspecified"))
      (node (ref "UE1") (pin "34") (pinfunction "CS/SK_34") (pintype "unspecified"))
    )
    (net (code "117") (name "/CS_ADDR0") (class "Default")
      (node (ref "H3") (pin "1") (pinfunction "1_1") (pintype "input"))
      (node (ref "U4") (pin "2") (pinfunction "A0_2") (pintype "input"))
    )
    (net (code "118") (name "/CS_ADDR1") (class "Default")
      (node (ref "H3") (pin "2") (pinfunction "2_2") (pintype "input"))
      (node (ref "U4") (pin "3") (pinfunction "A1_3") (pintype "input"))
    )
    (net (code "119") (name "/CS_ADDR2") (class "Default")
      (node (ref "H3") (pin "3") (pinfunction "3_3") (pintype "input"))
      (node (ref "U4") (pin "21") (pinfunction "A2_21") (pintype "input"))
    )
    (net (code "120") (name "/CS_ADDR3") (class "Default")
      (node (ref "H3") (pin "4") (pinfunction "4_4") (pintype "input"))
      (node (ref "U4") (pin "22") (pinfunction "A3_22") (pintype "input"))
    )
    (net (code "121") (name "/DATA") (class "Default")
      (node (ref "H3") (pin "7") (pinfunction "7_7") (pintype "input"))
      (node (ref "UA0") (pin "36") (pinfunction "DAT_36") (pintype "unspecified"))
      (node (ref "UA1") (pin "36") (pinfunction "DAT_36") (pintype "unspecified"))
      (node (ref "UB0") (pin "36") (pinfunction "DAT_36") (pintype "unspecified"))
      (node (ref "UB1") (pin "36") (pinfunction "DAT_36") (pintype "unspecified"))
      (node (ref "UC0") (pin "36") (pinfunction "DAT_36") (pintype "unspecified"))
      (node (ref "UC1") (pin "36") (pinfunction "DAT_36") (pintype "unspecified"))
      (node (ref "UD0") (pin "36") (pinfunction "DAT_36") (pintype "unspecified"))
      (node (ref "UD1") (pin "36") (pinfunction "DAT_36") (pintype "unspecified"))
      (node (ref "UE0") (pin "36") (pinfunction "DAT_36") (pintype "unspecified"))
      (node (ref "UE1") (pin "36") (pinfunction "DAT_36") (pintype "unspecified"))
    )
    (net (code "122") (name "/DE0") (class "Default")
      (node (ref "UD1") (pin "5") (pinfunction "X8_5") (pintype "unspecified"))
      (node (ref "UE1") (pin "5") (pinfunction "X8_5") (pintype "unspecified"))
    )
    (net (code "123") (name "/DE1") (class "Default")
      (node (ref "UD1") (pin "6") (pinfunction "X9_6") (pintype "unspecified"))
      (node (ref "UE1") (pin "6") (pinfunction "X9_6") (pintype "unspecified"))
    )
    (net (code "124") (name "/DE2") (class "Default")
      (node (ref "UD1") (pin "7") (pinfunction "X10_7") (pintype "unspecified"))
      (node (ref "UE1") (pin "7") (pinfunction "X10_7") (pintype "unspecified"))
    )
    (net (code "125") (name "/DE3") (class "Default")
      (node (ref "UD1") (pin "8") (pinfunction "X11_8") (pintype "unspecified"))
      (node (ref "UE1") (pin "8") (pinfunction "X11_8") (pintype "unspecified"))
    )
    (net (code "126") (name "/DE4") (class "Default")
      (node (ref "UD1") (pin "25") (pinfunction "X12_25") (pintype "unspecified"))
      (node (ref "UE1") (pin "25") (pinfunction "X12_25") (pintype "unspecified"))
    )
    (net (code "127") (name "/DE5") (class "Default")
      (node (ref "UD1") (pin "24") (pinfunction "X13_24") (pintype "unspecified"))
      (node (ref "UE1") (pin "24") (pinfunction "X13_24") (pintype "unspecified"))
    )
    (net (code "128") (name "/DE6") (class "Default")
      (node (ref "UD1") (pin "1") (pinfunction "X14_1") (pintype "unspecified"))
      (node (ref "UE1") (pin "1") (pinfunction "X14_1") (pintype "unspecified"))
    )
    (net (code "129") (name "/DE7") (class "Default")
      (node (ref "UD1") (pin "2") (pinfunction "X15_2") (pintype "unspecified"))
      (node (ref "UE1") (pin "2") (pinfunction "X15_2") (pintype "unspecified"))
    )
    (net (code "130") (name "/RESET") (class "Default")
      (node (ref "H3") (pin "6") (pinfunction "6_6") (pintype "input"))
      (node (ref "UA0") (pin "41") (pinfunction "RST_41") (pintype "unspecified"))
      (node (ref "UA1") (pin "41") (pinfunction "RST_41") (pintype "unspecified"))
      (node (ref "UB0") (pin "41") (pinfunction "RST_41") (pintype "unspecified"))
      (node (ref "UB1") (pin "41") (pinfunction "RST_41") (pintype "unspecified"))
      (node (ref "UC0") (pin "41") (pinfunction "RST_41") (pintype "unspecified"))
      (node (ref "UC1") (pin "41") (pinfunction "RST_41") (pintype "unspecified"))
      (node (ref "UD0") (pin "41") (pinfunction "RST_41") (pintype "unspecified"))
      (node (ref "UD1") (pin "41") (pinfunction "RST_41") (pintype "unspecified"))
      (node (ref "UE0") (pin "41") (pinfunction "RST_41") (pintype "unspecified"))
      (node (ref "UE1") (pin "41") (pinfunction "RST_41") (pintype "unspecified"))
    )
    (net (code "131") (name "/STB#") (class "Default")
      (node (ref "H3") (pin "5") (pinfunction "5_5") (pintype "input"))
      (node (ref "U4") (pin "23") (pinfunction "E#_23") (pintype "input"))
    )
    (net (code "132") (name "/STB_A0") (class "Default")
      (node (ref "U4") (pin "11") (pinfunction "Q0_11") (pintype "output"))
      (node (ref "UA0") (pin "14") (pinfunction "STB_14") (pintype "unspecified"))
    )
    (net (code "133") (name "/STB_A1") (class "Default")
      (node (ref "U4") (pin "9") (pinfunction "Q1_9") (pintype "output"))
      (node (ref "UA1") (pin "14") (pinfunction "STB_14") (pintype "unspecified"))
    )
    (net (code "134") (name "/STB_B0") (class "Default")
      (node (ref "U4") (pin "10") (pinfunction "Q2_10") (pintype "output"))
      (node (ref "UB0") (pin "14") (pinfunction "STB_14") (pintype "unspecified"))
    )
    (net (code "135") (name "/STB_B1") (class "Default")
      (node (ref "U4") (pin "8") (pinfunction "Q3_8") (pintype "output"))
      (node (ref "UB1") (pin "14") (pinfunction "STB_14") (pintype "unspecified"))
    )
    (net (code "136") (name "/STB_C0") (class "Default")
      (node (ref "U4") (pin "7") (pinfunction "Q4_7") (pintype "output"))
      (node (ref "UC0") (pin "14") (pinfunction "STB_14") (pintype "unspecified"))
    )
    (net (code "137") (name "/STB_C1") (class "Default")
      (node (ref "U4") (pin "6") (pinfunction "Q5_6") (pintype "output"))
      (node (ref "UC1") (pin "14") (pinfunction "STB_14") (pintype "unspecified"))
    )
    (net (code "138") (name "/STB_D0") (class "Default")
      (node (ref "U4") (pin "5") (pinfunction "Q6_5") (pintype "output"))
      (node (ref "UD0") (pin "14") (pinfunction "STB_14") (pintype "unspecified"))
    )
    (net (code "139") (name "/STB_D1") (class "Default")
      (node (ref "U4") (pin "4") (pinfunction "Q7_4") (pintype "output"))
      (node (ref "UD1") (pin "14") (pinfunction "STB_14") (pintype "unspecified"))
    )
    (net (code "140") (name "/STB_E0") (class "Default")
      (node (ref "U4") (pin "18") (pinfunction "Q8_18") (pintype "output"))
      (node (ref "UE0") (pin "14") (pinfunction "STB_14") (pintype "unspecified"))
    )
    (net (code "141") (name "/STB_E1") (class "Default")
      (node (ref "U4") (pin "17") (pinfunction "Q9_17") (pintype "output"))
      (node (ref "UE1") (pin "14") (pinfunction "STB_14") (pintype "unspecified"))
    )
    (net (code "142") (name "/TOP_RAIL") (class "Default")
      (node (ref "H1") (pin "2") (pinfunction "2_2") (pintype "input"))
    )
    (net (code "143") (name "GND") (class "Default")
      (node (ref "C1") (pin "1") (pinfunction "1_1") (pintype "input"))
      (node (ref "C2") (pin "1") (pinfunction "1_1") (pintype "input"))
      (node (ref "C3") (pin "2") (pinfunction "2_2") (pintype "input"))
      (node (ref "C8") (pin "2") (pinfunction "2_2") (pintype "input"))
      (node (ref "C9") (pin "2") (pinfunction "2_2") (pintype "input"))
      (node (ref "D4") (pin "1") (pinfunction "C_1") (pintype "unspecified"))
      (node (ref "R1") (pin "1") (pinfunction "1_1") (pintype "input"))
      (node (ref "R2") (pin "1") (pinfunction "1_1") (pintype "input"))
      (node (ref "U1") (pin "3") (pinfunction "GND_3") (pintype "input"))
      (node (ref "U2") (pin "1") (pinfunction "GND_1") (pintype "unspecified"))
      (node (ref "U4") (pin "12") (pinfunction "GND_12") (pintype "input"))
      (node (ref "UA0") (pin "10") (pinfunction "P/-S_10") (pintype "unspecified"))
      (node (ref "UA0") (pin "12") (pinfunction "GND_12") (pintype "unspecified"))
      (node (ref "UA0") (pin "18") (pinfunction "AX1_18") (pintype "unspecified"))
      (node (ref "UA0") (pin "19") (pinfunction "AX2_19") (pintype "unspecified"))
      (node (ref "UA0") (pin "20") (pinfunction "AY0_20") (pintype "unspecified"))
      (node (ref "UA0") (pin "21") (pinfunction "AY1_21") (pintype "unspecified"))
      (node (ref "UA0") (pin "40") (pinfunction "AY2_40") (pintype "unspecified"))
      (node (ref "UA0") (pin "42") (pinfunction "AX3_42") (pintype "unspecified"))
      (node (ref "UA0") (pin "43") (pinfunction "AX0_43") (pintype "unspecified"))
      (node (ref "UA1") (pin "10") (pinfunction "P/-S_10") (pintype "unspecified"))
      (node (ref "UA1") (pin "12") (pinfunction "GND_12") (pintype "unspecified"))
      (node (ref "UA1") (pin "18") (pinfunction "AX1_18") (pintype "unspecified"))
      (node (ref "UA1") (pin "19") (pinfunction "AX2_19") (pintype "unspecified"))
      (node (ref "UA1") (pin "20") (pinfunction "AY0_20") (pintype "unspecified"))
      (node (ref "UA1") (pin "21") (pinfunction "AY1_21") (pintype "unspecified"))
      (node (ref "UA1") (pin "40") (pinfunction "AY2_40") (pintype "unspecified"))
      (node (ref "UA1") (pin "42") (pinfunction "AX3_42") (pintype "unspecified"))
      (node (ref "UA1") (pin "43") (pinfunction "AX0_43") (pintype "unspecified"))
      (node (ref "UB0") (pin "10") (pinfunction "P/-S_10") (pintype "unspecified"))
      (node (ref "UB0") (pin "12") (pinfunction "GND_12") (pintype "unspecified"))
      (node (ref "UB0") (pin "18") (pinfunction "AX1_18") (pintype "unspecified"))
      (node (ref "UB0") (pin "19") (pinfunction "AX2_19") (pintype "unspecified"))
      (node (ref "UB0") (pin "20") (pinfunction "AY0_20") (pintype "unspecified"))
      (node (ref "UB0") (pin "21") (pinfunction "AY1_21") (pintype "unspecified"))
      (node (ref "UB0") (pin "40") (pinfunction "AY2_40") (pintype "unspecified"))
      (node (ref "UB0") (pin "42") (pinfunction "AX3_42") (pintype "unspecified"))
      (node (ref "UB0") (pin "43") (pinfunction "AX0_43") (pintype "unspecified"))
      (node (ref "UB1") (pin "10") (pinfunction "P/-S_10") (pintype "unspecified"))
      (node (ref "UB1") (pin "12") (pinfunction "GND_12") (pintype "unspecified"))
      (node (ref "UB1") (pin "18") (pinfunction "AX1_18") (pintype "unspecified"))
      (node (ref "UB1") (pin "19") (pinfunction "AX2_19") (pintype "unspecified"))
      (node (ref "UB1") (pin "20") (pinfunction "AY0_20") (pintype "unspecified"))
      (node (ref "UB1") (pin "21") (pinfunction "AY1_21") (pintype "unspecified"))
      (node (ref "UB1") (pin "40") (pinfunction "AY2_40") (pintype "unspecified"))
      (node (ref "UB1") (pin "42") (pinfunction "AX3_42") (pintype "unspecified"))
      (node (ref "UB1") (pin "43") (pinfunction "AX0_43") (pintype "unspecified"))
      (node (ref "UC0") (pin "10") (pinfunction "P/-S_10") (pintype "unspecified"))
      (node (ref "UC0") (pin "12") (pinfunction "GND_12") (pintype "unspecified"))
      (node (ref "UC0") (pin "18") (pinfunction "AX1_18") (pintype "unspecified"))
      (node (ref "UC0") (pin "19") (pinfunction "AX2_19") (pintype "unspecified"))
      (node (ref "UC0") (pin "20") (pinfunction "AY0_20") (pintype "unspecified"))
      (node (ref "UC0") (pin "21") (pinfunction "AY1_21") (pintype "unspecified"))
      (node (ref "UC0") (pin "40") (pinfunction "AY2_40") (pintype "unspecified"))
      (node (ref "UC0") (pin "42") (pinfunction "AX3_42") (pintype "unspecified"))
      (node (ref "UC0") (pin "43") (pinfunction "AX0_43") (pintype "unspecified"))
      (node (ref "UC1") (pin "10") (pinfunction "P/-S_10") (pintype "unspecified"))
      (node (ref "UC1") (pin "12") (pinfunction "GND_12") (pintype "unspecified"))
      (node (ref "UC1") (pin "18") (pinfunction "AX1_18") (pintype "unspecified"))
      (node (ref "UC1") (pin "19") (pinfunction "AX2_19") (pintype "unspecified"))
      (node (ref "UC1") (pin "20") (pinfunction "AY0_20") (pintype "unspecified"))
      (node (ref "UC1") (pin "21") (pinfunction "AY1_21") (pintype "unspecified"))
      (node (ref "UC1") (pin "40") (pinfunction "AY2_40") (pintype "unspecified"))
      (node (ref "UC1") (pin "42") (pinfunction "AX3_42") (pintype "unspecified"))
      (node (ref "UC1") (pin "43") (pinfunction "AX0_43") (pintype "unspecified"))
      (node (ref "UD0") (pin "10") (pinfunction "P/-S_10") (pintype "unspecified"))
      (node (ref "UD0") (pin "12") (pinfunction "GND_12") (pintype "unspecified"))
      (node (ref "UD0") (pin "18") (pinfunction "AX1_18") (pintype "unspecified"))
      (node (ref "UD0") (pin "19") (pinfunction "AX2_19") (pintype "unspecified"))
      (node (ref "UD0") (pin "20") (pinfunction "AY0_20") (pintype "unspecified"))
      (node (ref "UD0") (pin "21") (pinfunction "AY1_21") (pintype "unspecified"))
      (node (ref "UD0") (pin "40") (pinfunction "AY2_40") (pintype "unspecified"))
      (node (ref "UD0") (pin "42") (pinfunction "AX3_42") (pintype "unspecified"))
      (node (ref "UD0") (pin "43") (pinfunction "AX0_43") (pintype "unspecified"))
      (node (ref "UD1") (pin "10") (pinfunction "P/-S_10") (pintype "unspecified"))
      (node (ref "UD1") (pin "12") (pinfunction "GND_12") (pintype "unspecified"))
      (node (ref "UD1") (pin "18") (pinfunction "AX1_18") (pintype "unspecified"))
      (node (ref "UD1") (pin "19") (pinfunction "AX2_19") (pintype "unspecified"))
      (node (ref "UD1") (pin "20") (pinfunction "AY0_20") (pintype "unspecified"))
      (node (ref "UD1") (pin "21") (pinfunction "AY1_21") (pintype "unspecified"))
      (node (ref "UD1") (pin "40") (pinfunction "AY2_40") (pintype "unspecified"))
      (node (ref "UD1") (pin "42") (pinfunction "AX3_42") (pintype "unspecified"))
      (node (ref "UD1") (pin "43") (pinfunction "AX0_43") (pintype "unspecified"))
      (node (ref "UE0") (pin "10") (pinfunction "P/-S_10") (pintype "unspecified"))
      (node (ref "UE0") (pin "12") (pinfunction "GND_12") (pintype "unspecified"))
      (node (ref "UE0") (pin "18") (pinfunction "AX1_18") (pintype "unspecified"))
      (node (ref "UE0") (pin "19") (pinfunction "AX2_19") (pintype "unspecified"))
      (node (ref "UE0") (pin "20") (pinfunction "AY0_20") (pintype "unspecified"))
      (node (ref "UE0") (pin "21") (pinfunction "AY1_21") (pintype "unspecified"))
      (node (ref "UE0") (pin "40") (pinfunction "AY2_40") (pintype "unspecified"))
      (node (ref "UE0") (pin "42") (pinfunction "AX3_42") (pintype "unspecified"))
      (node (ref "UE0") (pin "43") (pinfunction "AX0_43") (pintype "unspecified"))
      (node (ref "UE1") (pin "10") (pinfunction "P/-S_10") (pintype "unspecified"))
      (node (ref "UE1") (pin "12") (pinfunction "GND_12") (pintype "unspecified"))
      (node (ref "UE1") (pin "18") (pinfunction "AX1_18") (pintype "unspecified"))
      (node (ref "UE1") (pin "19") (pinfunction "AX2_19") (pintype "unspecified"))
      (node (ref "UE1") (pin "20") (pinfunction "AY0_20") (pintype "unspecified"))
      (node (ref "UE1") (pin "21") (pinfunction "AY1_21") (pintype "unspecified"))
      (node (ref "UE1") (pin "40") (pinfunction "AY2_40") (pintype "unspecified"))
      (node (ref "UE1") (pin "42") (pinfunction "AX3_42") (pintype "unspecified"))
      (node (ref "UE1") (pin "43") (pinfunction "AX0_43") (pintype "unspecified"))
      (node (ref "USB1") (pin "A12") (pinfunction "GND_A12") (pintype "unspecified"))
      (node (ref "USB1") (pin "B12") (pinfunction "GND_B12") (pintype "unspecified"))
    )
    (net (code "144") (name "Net-(D1-C)") (class "Default")
      (node (ref "C5") (pin "1") (pinfunction "1_1") (pintype "input"))
      (node (ref "D1") (pin "1") (pinfunction "C_1") (pintype "unspecified"))
      (node (ref "D2") (pin "2") (pinfunction "A_2") (pintype "unspecified"))
    )
    (net (code "145") (name "Net-(D3-A)") (class "Default")
      (node (ref "C7") (pin "2") (pinfunction "2_2") (pintype "input"))
      (node (ref "D3") (pin "2") (pinfunction "A_2") (pintype "unspecified"))
      (node (ref "D4") (pin "2") (pinfunction "A_2") (pintype "unspecified"))
      (node (ref "D5") (pin "1") (pinfunction "C_1") (pintype "unspecified"))
    )
    (net (code "146") (name "Net-(D3-C)") (class "Default")
      (node (ref "C1") (pin "2") (pinfunction "2_2") (pintype "input"))
      (node (ref "D3") (pin "1") (pinfunction "C_1") (pintype "unspecified"))
      (node (ref "U1") (pin "5") (pinfunction "VOUT_5") (pintype "input"))
    )
    (net (code "147") (name "Net-(U1-CAP+)") (class "Default")
      (node (ref "C5") (pin "2") (pinfunction "2_2") (pintype "input"))
      (node (ref "C6") (pin "1") (pinfunction "1_1") (pintype "input"))
      (node (ref "U1") (pin "2") (pinfunction "CAP+_2") (pintype "input"))
    )
    (net (code "148") (name "Net-(U1-CAP–)") (class "Default")
      (node (ref "C6") (pin "2") (pinfunction "2_2") (pintype "input"))
      (node (ref "C7") (pin "1") (pinfunction "1_1") (pintype "input"))
      (node (ref "U1") (pin "4") (pinfunction "CAP–_4") (pintype "input"))
    )
    (net (code "149") (name "Net-(USB1-CC1)") (class "Default")
      (node (ref "R1") (pin "2") (pinfunction "2_2") (pintype "input"))
      (node (ref "USB1") (pin "A5") (pinfunction "CC1_A5") (pintype "unspecified"))
    )
    (net (code "150") (name "Net-(USB1-CC2)") (class "Default")
      (node (ref "R2") (pin "2") (pinfunction "2_2") (pintype "input"))
      (node (ref "USB1") (pin "B5") (pinfunction "CC2_B5") (pintype "unspecified"))
    )
    (net (code "151") (name "VDD") (class "Default")
      (node (ref "C3") (pin "1") (pinfunction "1_1") (pintype "input"))
      (node (ref "D2") (pin "1") (pinfunction "C_1") (pintype "unspecified"))
      (node (ref "UA0") (pin "38") (pinfunction "VDD_38") (pintype "unspecified"))
      (node (ref "UA1") (pin "38") (pinfunction "VDD_38") (pintype "unspecified"))
      (node (ref "UB0") (pin "38") (pinfunction "VDD_38") (pintype "unspecified"))
      (node (ref "UB1") (pin "38") (pinfunction "VDD_38") (pintype "unspecified"))
      (node (ref "UC0") (pin "38") (pinfunction "VDD_38") (pintype "unspecified"))
      (node (ref "UC1") (pin "38") (pinfunction "VDD_38") (pintype "unspecified"))
      (node (ref "UD0") (pin "38") (pinfunction "VDD_38") (pintype "unspecified"))
      (node (ref "UD1") (pin "38") (pinfunction "VDD_38") (pintype "unspecified"))
      (node (ref "UE0") (pin "38") (pinfunction "VDD_38") (pintype "unspecified"))
      (node (ref "UE1") (pin "38") (pinfunction "VDD_38") (pintype "unspecified"))
    )
    (net (code "152") (name "VEE") (class "Default")
      (node (ref "C2") (pin "2") (pinfunction "2_2") (pintype "input"))
      (node (ref "D5") (pin "2") (pinfunction "A_2") (pintype "unspecified"))
      (node (ref "UA0") (pin "16") (pinfunction "VEE_16") (pintype "unspecified"))
      (node (ref "UA1") (pin "16") (pinfunction "VEE_16") (pintype "unspecified"))
      (node (ref "UB0") (pin "16") (pinfunction "VEE_16") (pintype "unspecified"))
      (node (ref "UB1") (pin "16") (pinfunction "VEE_16") (pintype "unspecified"))
      (node (ref "UC0") (pin "16") (pinfunction "VEE_16") (pintype "unspecified"))
      (node (ref "UC1") (pin "16") (pinfunction "VEE_16") (pintype "unspecified"))
      (node (ref "UD0") (pin "16") (pinfunction "VEE_16") (pintype "unspecified"))
      (node (ref "UD1") (pin "16") (pinfunction "VEE_16") (pintype "unspecified"))
      (node (ref "UE0") (pin "16") (pinfunction "VEE_16") (pintype "unspecified"))
      (node (ref "UE1") (pin "16") (pinfunction "VEE_16") (pintype "unspecified"))
    )
    (net (code "153") (name "unconnected-(U1-FB{slash}SHDN-Pad1)") (class "Default")
      (node (ref "U1") (pin "1") (pinfunction "FB/SHDN_1") (pintype "input+no_connect"))
    )
    (net (code "154") (name "unconnected-(U1-OSC-Pad7)") (class "Default")
      (node (ref "U1") (pin "7") (pinfunction "OSC_7") (pintype "input+no_connect"))
    )
    (net (code "155") (name "unconnected-(U1-VREF-Pad6)") (class "Default")
      (node (ref "U1") (pin "6") (pinfunction "VREF_6") (pintype "input+no_connect"))
    )
    (net (code "156") (name "unconnected-(U4-Q10-Pad20)") (class "Default")
      (node (ref "U4") (pin "20") (pinfunction "Q10_20") (pintype "output+no_connect"))
    )
    (net (code "157") (name "unconnected-(U4-Q11-Pad19)") (class "Default")
      (node (ref "U4") (pin "19") (pinfunction "Q11_19") (pintype "output+no_connect"))
    )
    (net (code "158") (name "unconnected-(U4-Q12-Pad14)") (class "Default")
      (node (ref "U4") (pin "14") (pinfunction "Q12_14") (pintype "output+no_connect"))
    )
    (net (code "159") (name "unconnected-(U4-Q13-Pad13)") (class "Default")
      (node (ref "U4") (pin "13") (pinfunction "Q13_13") (pintype "output+no_connect"))
    )
    (net (code "160") (name "unconnected-(U4-Q14-Pad16)") (class "Default")
      (node (ref "U4") (pin "16") (pinfunction "Q14_16") (pintype "output+no_connect"))
    )
    (net (code "161") (name "unconnected-(U4-Q15-Pad15)") (class "Default")
      (node (ref "U4") (pin "15") (pinfunction "Q15_15") (pintype "output+no_connect"))
    )
    (net (code "162") (name "unconnected-(UA0-NC-Pad9)") (class "Default")
      (node (ref "UA0") (pin "9") (pinfunction "NC_9") (pintype "unspecified+no_connect"))
    )
    (net (code "163") (name "unconnected-(UA0-NC-Pad22)") (class "Default")
      (node (ref "UA0") (pin "22") (pinfunction "NC_22") (pintype "unspecified+no_connect"))
    )
    (net (code "164") (name "unconnected-(UA0-NC-Pad23)") (class "Default")
      (node (ref "UA0") (pin "23") (pinfunction "NC_23") (pintype "unspecified+no_connect"))
    )
    (net (code "165") (name "unconnected-(UA0-NC-Pad32)") (class "Default")
      (node (ref "UA0") (pin "32") (pinfunction "NC_32") (pintype "unspecified+no_connect"))
    )
    (net (code "166") (name "unconnected-(UA0-NC-Pad44)") (class "Default")
      (node (ref "UA0") (pin "44") (pinfunction "NC_44") (pintype "unspecified+no_connect"))
    )
    (net (code "167") (name "unconnected-(UA1-NC-Pad9)") (class "Default")
      (node (ref "UA1") (pin "9") (pinfunction "NC_9") (pintype "unspecified+no_connect"))
    )
    (net (code "168") (name "unconnected-(UA1-NC-Pad22)") (class "Default")
      (node (ref "UA1") (pin "22") (pinfunction "NC_22") (pintype "unspecified+no_connect"))
    )
    (net (code "169") (name "unconnected-(UA1-NC-Pad23)") (class "Default")
      (node (ref "UA1") (pin "23") (pinfunction "NC_23") (pintype "unspecified+no_connect"))
    )
    (net (code "170") (name "unconnected-(UA1-NC-Pad32)") (class "Default")
      (node (ref "UA1") (pin "32") (pinfunction "NC_32") (pintype "unspecified+no_connect"))
    )
    (net (code "171") (name "unconnected-(UA1-NC-Pad44)") (class "Default")
      (node (ref "UA1") (pin "44") (pinfunction "NC_44") (pintype "unspecified+no_connect"))
    )
    (net (code "172") (name "unconnected-(UB0-NC-Pad9)") (class "Default")
      (node (ref "UB0") (pin "9") (pinfunction "NC_9") (pintype "unspecified+no_connect"))
    )
    (net (code "173") (name "unconnected-(UB0-NC-Pad22)") (class "Default")
      (node (ref "UB0") (pin "22") (pinfunction "NC_22") (pintype "unspecified+no_connect"))
    )
    (net (code "174") (name "unconnected-(UB0-NC-Pad23)") (class "Default")
      (node (ref "UB0") (pin "23") (pinfunction "NC_23") (pintype "unspecified+no_connect"))
    )
    (net (code "175") (name "unconnected-(UB0-NC-Pad32)") (class "Default")
      (node (ref "UB0") (pin "32") (pinfunction "NC_32") (pintype "unspecified+no_connect"))
    )
    (net (code "176") (name "unconnected-(UB0-NC-Pad44)") (class "Default")
      (node (ref "UB0") (pin "44") (pinfunction "NC_44") (pintype "unspecified+no_connect"))
    )
    (net (code "177") (name "unconnected-(UB1-NC-Pad9)") (class "Default")
      (node (ref "UB1") (pin "9") (pinfunction "NC_9") (pintype "unspecified+no_connect"))
    )
    (net (code "178") (name "unconnected-(UB1-NC-Pad22)") (class "Default")
      (node (ref "UB1") (pin "22") (pinfunction "NC_22") (pintype "unspecified+no_connect"))
    )
    (net (code "179") (name "unconnected-(UB1-NC-Pad23)") (class "Default")
      (node (ref "UB1") (pin "23") (pinfunction "NC_23") (pintype "unspecified+no_connect"))
    )
    (net (code "180") (name "unconnected-(UB1-NC-Pad32)") (class "Default")
      (node (ref "UB1") (pin "32") (pinfunction "NC_32") (pintype "unspecified+no_connect"))
    )
    (net (code "181") (name "unconnected-(UB1-NC-Pad44)") (class "Default")
      (node (ref "UB1") (pin "44") (pinfunction "NC_44") (pintype "unspecified+no_connect"))
    )
    (net (code "182") (name "unconnected-(UC0-NC-Pad9)") (class "Default")
      (node (ref "UC0") (pin "9") (pinfunction "NC_9") (pintype "unspecified+no_connect"))
    )
    (net (code "183") (name "unconnected-(UC0-NC-Pad22)") (class "Default")
      (node (ref "UC0") (pin "22") (pinfunction "NC_22") (pintype "unspecified+no_connect"))
    )
    (net (code "184") (name "unconnected-(UC0-NC-Pad23)") (class "Default")
      (node (ref "UC0") (pin "23") (pinfunction "NC_23") (pintype "unspecified+no_connect"))
    )
    (net (code "185") (name "unconnected-(UC0-NC-Pad32)") (class "Default")
      (node (ref "UC0") (pin "32") (pinfunction "NC_32") (pintype "unspecified+no_connect"))
    )
    (net (code "186") (name "unconnected-(UC0-NC-Pad44)") (class "Default")
      (node (ref "UC0") (pin "44") (pinfunction "NC_44") (pintype "unspecified+no_connect"))
    )
    (net (code "187") (name "unconnected-(UC1-NC-Pad9)") (class "Default")
      (node (ref "UC1") (pin "9") (pinfunction "NC_9") (pintype "unspecified+no_connect"))
    )
    (net (code "188") (name "unconnected-(UC1-NC-Pad22)") (class "Default")
      (node (ref "UC1") (pin "22") (pinfunction "NC_22") (pintype "unspecified+no_connect"))
    )
    (net (code "189") (name "unconnected-(UC1-NC-Pad23)") (class "Default")
      (node (ref "UC1") (pin "23") (pinfunction "NC_23") (pintype "unspecified+no_connect"))
    )
    (net (code "190") (name "unconnected-(UC1-NC-Pad32)") (class "Default")
      (node (ref "UC1") (pin "32") (pinfunction "NC_32") (pintype "unspecified+no_connect"))
    )
    (net (code "191") (name "unconnected-(UC1-NC-Pad44)") (class "Default")
      (node (ref "UC1") (pin "44") (pinfunction "NC_44") (pintype "unspecified+no_connect"))
    )
    (net (code "192") (name "unconnected-(UD0-NC-Pad9)") (class "Default")
      (node (ref "UD0") (pin "9") (pinfunction "NC_9") (pintype "unspecified+no_connect"))
    )
    (net (code "193") (name "unconnected-(UD0-NC-Pad22)") (class "Default")
      (node (ref "UD0") (pin "22") (pinfunction "NC_22") (pintype "unspecified+no_connect"))
    )
    (net (code "194") (name "unconnected-(UD0-NC-Pad23)") (class "Default")
      (node (ref "UD0") (pin "23") (pinfunction "NC_23") (pintype "unspecified+no_connect"))
    )
    (net (code "195") (name "unconnected-(UD0-NC-Pad32)") (class "Default")
      (node (ref "UD0") (pin "32") (pinfunction "NC_32") (pintype "unspecified+no_connect"))
    )
    (net (code "196") (name "unconnected-(UD0-NC-Pad44)") (class "Default")
      (node (ref "UD0") (pin "44") (pinfunction "NC_44") (pintype "unspecified+no_connect"))
    )
    (net (code "197") (name "unconnected-(UD1-NC-Pad9)") (class "Default")
      (node (ref "UD1") (pin "9") (pinfunction "NC_9") (pintype "unspecified+no_connect"))
    )
    (net (code "198") (name "unconnected-(UD1-NC-Pad22)") (class "Default")
      (node (ref "UD1") (pin "22") (pinfunction "NC_22") (pintype "unspecified+no_connect"))
    )
    (net (code "199") (name "unconnected-(UD1-NC-Pad23)") (class "Default")
      (node (ref "UD1") (pin "23") (pinfunction "NC_23") (pintype "unspecified+no_connect"))
    )
    (net (code "200") (name "unconnected-(UD1-NC-Pad32)") (class "Default")
      (node (ref "UD1") (pin "32") (pinfunction "NC_32") (pintype "unspecified+no_connect"))
    )
    (net (code "201") (name "unconnected-(UD1-NC-Pad44)") (class "Default")
      (node (ref "UD1") (pin "44") (pinfunction "NC_44") (pintype "unspecified+no_connect"))
    )
    (net (code "202") (name "unconnected-(UE0-NC-Pad9)") (class "Default")
      (node (ref "UE0") (pin "9") (pinfunction "NC_9") (pintype "unspecified+no_connect"))
    )
    (net (code "203") (name "unconnected-(UE0-NC-Pad22)") (class "Default")
      (node (ref "UE0") (pin "22") (pinfunction "NC_22") (pintype "unspecified+no_connect"))
    )
    (net (code "204") (name "unconnected-(UE0-NC-Pad23)") (class "Default")
      (node (ref "UE0") (pin "23") (pinfunction "NC_23") (pintype "unspecified+no_connect"))
    )
    (net (code "205") (name "unconnected-(UE0-NC-Pad32)") (class "Default")
      (node (ref "UE0") (pin "32") (pinfunction "NC_32") (pintype "unspecified+no_connect"))
    )
    (net (code "206") (name "unconnected-(UE0-NC-Pad44)") (class "Default")
      (node (ref "UE0") (pin "44") (pinfunction "NC_44") (pintype "unspecified+no_connect"))
    )
    (net (code "207") (name "unconnected-(UE1-NC-Pad9)") (class "Default")
      (node (ref "UE1") (pin "9") (pinfunction "NC_9") (pintype "unspecified+no_connect"))
    )
    (net (code "208") (name "unconnected-(UE1-NC-Pad22)") (class "Default")
      (node (ref "UE1") (pin "22") (pinfunction "NC_22") (pintype "unspecified+no_connect"))
    )
    (net (code "209") (name "unconnected-(UE1-NC-Pad23)") (class "Default")
      (node (ref "UE1") (pin "23") (pinfunction "NC_23") (pintype "unspecified+no_connect"))
    )
    (net (code "210") (name "unconnected-(UE1-NC-Pad32)") (class "Default")
      (node (ref "UE1") (pin "32") (pinfunction "NC_32") (pintype "unspecified+no_connect"))
    )
    (net (code "211") (name "unconnected-(UE1-NC-Pad44)") (class "Default")
      (node (ref "UE1") (pin "44") (pinfunction "NC_44") (pintype "unspecified+no_connect"))
    )
    (net (code "212") (name "unconnected-(USB1-EH-Pad7)") (class "Default")
      (node (ref "USB1") (pin "7") (pinfunction "EH_7") (pintype "unspecified+no_connect"))
    )
  )
)
